# ESP32-WROM-32.net
KiCad netlist of a schematic drawn in Altium Designer
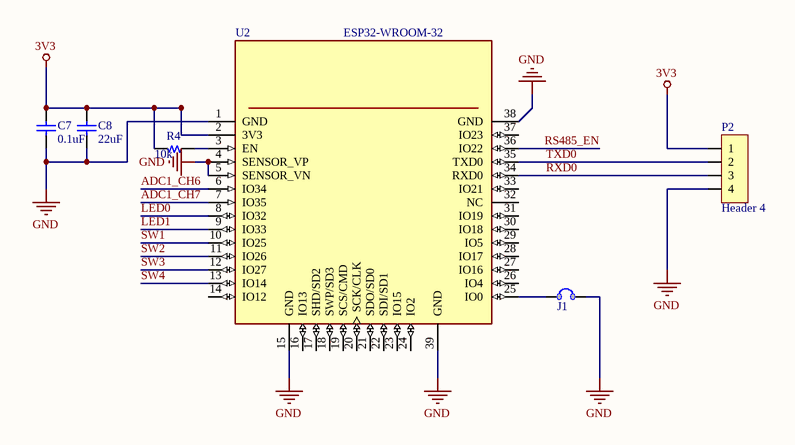
[diagram p0: ESP32-WROM-32.SchDoc]

(export (version "E")
  (design (tool "Eeschema 10.0.6"))
  (components
    (comp (ref "C7")
      (value "0.1uF")
      (footprint "C 0805")
      (description "Capacitor non-pol")
      (libsource (lib "chipfc_libs") (part "Capacitor NP"))
    )
    (comp (ref "C8")
      (value "22uF")
      (footprint "C 0805")
      (description "Capacitor non-pol")
      (libsource (lib "chipfc_libs") (part "Capacitor NP"))
    )
    (comp (ref "J1") (value "BOOT") (footprint "JUMP/2/Open") (libsource (lib "chipfc_libs") (part "JUMP 2")))
    (comp (ref "P2")
      (value "Header 4")
      (footprint "HDR/Header/4/BOX/WHITE")
      (description "Header, 4-Pin")
      (libsource (lib "connectors") (part "Header 4"))
    )
    (comp (ref "R4")
      (value "10k")
      (footprint "R 0805")
      (description "Resistor")
      (libsource (lib "chipfc_libs") (part "Resistor"))
    )
    (comp (ref "U2")
      (value "ESP32-WROOM-32")
      (footprint "MODULE_ESP32-WROOM-32")
      (fields (field (name "MF") "Espressif Systems") (field (name "MP") "ESP32-WROOM-32D"))
      (libsource (lib "ESP32") (part "ESP32-WROOM-32"))
    )
  )
  (nets
    (net (code "1") (name "/ADC1_CH6") (class "Default")
      (node (ref "U2") (pin "6") (pinfunction "IO34_6") (pintype "input"))
    )
    (net (code "2") (name "/ADC1_CH7") (class "Default")
      (node (ref "U2") (pin "7") (pinfunction "IO35_7") (pintype "input"))
    )
    (net (code "3") (name "/LED0") (class "Default")
      (node (ref "U2") (pin "8") (pinfunction "IO32_8") (pintype "bidirectional"))
    )
    (net (code "4") (name "/LED1") (class "Default")
      (node (ref "U2") (pin "9") (pinfunction "IO33_9") (pintype "bidirectional"))
    )
    (net (code "5") (name "/RS485_EN") (class "Default")
      (node (ref "U2") (pin "36") (pinfunction "IO22_36") (pintype "bidirectional"))
    )
    (net (code "6") (name "/RXD0") (class "Default")
      (node (ref "P2") (pin "3") (pinfunction "3_3") (pintype "passive"))
      (node (ref "U2") (pin "34") (pinfunction "RXD0_34") (pintype "bidirectional"))
    )
    (net (code "7") (name "/SW1") (class "Default")
      (node (ref "U2") (pin "10") (pinfunction "IO25_10") (pintype "bidirectional"))
    )
    (net (code "8") (name "/SW2") (class "Default")
      (node (ref "U2") (pin "11") (pinfunction "IO26_11") (pintype "bidirectional"))
    )
    (net (code "9") (name "/SW3") (class "Default")
      (node (ref "U2") (pin "12") (pinfunction "IO27_12") (pintype "bidirectional"))
    )
    (net (code "10") (name "/SW4") (class "Default")
      (node (ref "U2") (pin "13") (pinfunction "IO14_13") (pintype "bidirectional"))
    )
    (net (code "11") (name "/TXD0") (class "Default")
      (node (ref "P2") (pin "2") (pinfunction "2_2") (pintype "passive"))
      (node (ref "U2") (pin "35") (pinfunction "TXD0_35") (pintype "bidirectional"))
    )
    (net (code "12") (name "3V3") (class "Default")
      (node (ref "C7") (pin "1") (pinfunction "1_1") (pintype "passive"))
      (node (ref "C8") (pin "1") (pinfunction "1_1") (pintype "passive"))
      (node (ref "P2") (pin "1") (pinfunction "1_1") (pintype "passive"))
      (node (ref "R4") (pin "2") (pinfunction "2_2") (pintype "passive"))
      (node (ref "U2") (pin "2") (pinfunction "3V3_2") (pintype "power_in"))
    )
    (net (code "13") (name "GND") (class "Default")
      (node (ref "C7") (pin "2") (pinfunction "2_2") (pintype "passive"))
      (node (ref "C8") (pin "2") (pinfunction "2_2") (pintype "passive"))
      (node (ref "J1") (pin "2") (pinfunction "2_2") (pintype "passive"))
      (node (ref "P2") (pin "4") (pinfunction "4_4") (pintype "passive"))
      (node (ref "U2") (pin "1") (pinfunction "GND_1") (pintype "power_in"))
      (node (ref "U2") (pin "15") (pinfunction "GND_15") (pintype "power_in"))
      (node (ref "U2") (pin "38") (pinfunction "GND_38") (pintype "power_in"))
      (node (ref "U2") (pin "39") (pinfunction "GND_39") (pintype "power_in"))
      (node (ref "U2") (pin "4") (pinfunction "SENSOR_VP_4") (pintype "input"))
      (node (ref "U2") (pin "5") (pinfunction "SENSOR_VN_5") (pintype "input"))
    )
    (net (code "14") (name "Net-(U2-EN)") (class "Default")
      (node (ref "R4") (pin "1") (pinfunction "1_1") (pintype "passive"))
      (node (ref "U2") (pin "3") (pinfunction "EN_3") (pintype "input"))
    )
    (net (code "15") (name "Net-(U2-IO0)") (class "Default")
      (node (ref "J1") (pin "1") (pinfunction "1_1") (pintype "passive"))
      (node (ref "U2") (pin "25") (pinfunction "IO0_25") (pintype "bidirectional"))
    )
    (net (code "16") (name "unconnected-(U2-IO2-Pad24)") (class "Default")
      (node (ref "U2") (pin "24") (pinfunction "IO2_24") (pintype "bidirectional"))
    )
    (net (code "17") (name "unconnected-(U2-IO4-Pad26)") (class "Default")
      (node (ref "U2") (pin "26") (pinfunction "IO4_26") (pintype "bidirectional"))
    )
    (net (code "18") (name "unconnected-(U2-IO5-Pad29)") (class "Default")
      (node (ref "U2") (pin "29") (pinfunction "IO5_29") (pintype "bidirectional"))
    )
    (net (code "19") (name "unconnected-(U2-IO12-Pad14)") (class "Default")
      (node (ref "U2") (pin "14") (pinfunction "IO12_14") (pintype "bidirectional"))
    )
    (net (code "20") (name "unconnected-(U2-IO13-Pad16)") (class "Default")
      (node (ref "U2") (pin "16") (pinfunction "IO13_16") (pintype "bidirectional"))
    )
    (net (code "21") (name "unconnected-(U2-IO15-Pad23)") (class "Default")
      (node (ref "U2") (pin "23") (pinfunction "IO15_23") (pintype "bidirectional"))
    )
    (net (code "22") (name "unconnected-(U2-IO16-Pad27)") (class "Default")
      (node (ref "U2") (pin "27") (pinfunction "IO16_27") (pintype "bidirectional"))
    )
    (net (code "23") (name "unconnected-(U2-IO17-Pad28)") (class "Default")
      (node (ref "U2") (pin "28") (pinfunction "IO17_28") (pintype "bidirectional"))
    )
    (net (code "24") (name "unconnected-(U2-IO18-Pad30)") (class "Default")
      (node (ref "U2") (pin "30") (pinfunction "IO18_30") (pintype "bidirectional"))
    )
    (net (code "25") (name "unconnected-(U2-IO19-Pad31)") (class "Default")
      (node (ref "U2") (pin "31") (pinfunction "IO19_31") (pintype "bidirectional"))
    )
    (net (code "26") (name "unconnected-(U2-IO21-Pad33)") (class "Default")
      (node (ref "U2") (pin "33") (pinfunction "IO21_33") (pintype "bidirectional"))
    )
    (net (code "27") (name "unconnected-(U2-IO23-Pad37)") (class "Default")
      (node (ref "U2") (pin "37") (pinfunction "IO23_37") (pintype "bidirectional"))
    )
    (net (code "28") (name "unconnected-(U2-NC-Pad32)") (class "Default")
      (node (ref "U2") (pin "32") (pinfunction "NC_32") (pintype "power_in"))
    )
    (net (code "29") (name "unconnected-(U2-SCK{slash}CLK-Pad20)") (class "Default")
      (node (ref "U2") (pin "20") (pinfunction "SCK/CLK_20") (pintype "bidirectional"))
    )
    (net (code "30") (name "unconnected-(U2-SCS{slash}CMD-Pad19)") (class "Default")
      (node (ref "U2") (pin "19") (pinfunction "SCS/CMD_19") (pintype "bidirectional"))
    )
    (net (code "31") (name "unconnected-(U2-SDI{slash}SD1-Pad22)") (class "Default")
      (node (ref "U2") (pin "22") (pinfunction "SDI/SD1_22") (pintype "bidirectional"))
    )
    (net (code "32") (name "unconnected-(U2-SDO{slash}SD0-Pad21)") (class "Default")
      (node (ref "U2") (pin "21") (pinfunction "SDO/SD0_21") (pintype "bidirectional"))
    )
    (net (code "33") (name "unconnected-(U2-SHD{slash}SD2-Pad17)") (class "Default")
      (node (ref "U2") (pin "17") (pinfunction "SHD/SD2_17") (pintype "bidirectional"))
    )
    (net (code "34") (name "unconnected-(U2-SWP{slash}SD3-Pad18)") (class "Default")
      (node (ref "U2") (pin "18") (pinfunction "SWP/SD3_18") (pintype "bidirectional"))
    )
  )
)
